# Mezclador2.net
KiCad netlist of a schematic drawn in Altium Designer
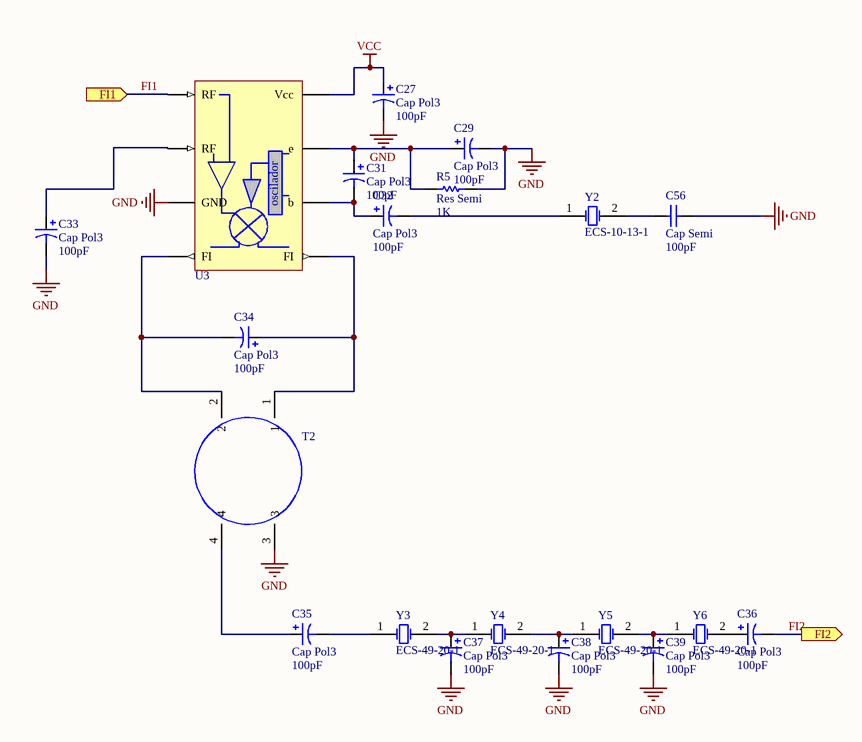
[diagram p0: Mezclador2.SchDoc]

(export (version "E")
  (design (tool "Eeschema 10.0.6"))
  (components
    (comp (ref "C27")
      (value "Cap Pol3")
      (footprint "C0805")
      (description "Polarized Capacitor (Surface Mount)")
      (fields (field (name "ALTIUM_VALUE") "100pF") (field (name "PUBLISHER") "Altium Limited"))
      (libsource (lib "Miscellaneous Devices") (part "Cap Pol3"))
    )
    (comp (ref "C29")
      (value "Cap Pol3")
      (footprint "C0805")
      (description "Polarized Capacitor (Surface Mount)")
      (fields (field (name "ALTIUM_VALUE") "100pF") (field (name "PUBLISHER") "Altium Limited"))
      (libsource (lib "Miscellaneous Devices") (part "Cap Pol3"))
    )
    (comp (ref "C31")
      (value "Cap Pol3")
      (footprint "C0805")
      (description "Polarized Capacitor (Surface Mount)")
      (fields (field (name "ALTIUM_VALUE") "100pF") (field (name "PUBLISHER") "Altium Limited"))
      (libsource (lib "Miscellaneous Devices") (part "Cap Pol3"))
    )
    (comp (ref "C32")
      (value "Cap Pol3")
      (footprint "C0805")
      (description "Polarized Capacitor (Surface Mount)")
      (fields (field (name "ALTIUM_VALUE") "100pF") (field (name "PUBLISHER") "Altium Limited"))
      (libsource (lib "Miscellaneous Devices") (part "Cap Pol3"))
    )
    (comp (ref "C33")
      (value "Cap Pol3")
      (footprint "C0805")
      (description "Polarized Capacitor (Surface Mount)")
      (fields (field (name "ALTIUM_VALUE") "100pF") (field (name "PUBLISHER") "Altium Limited"))
      (libsource (lib "Miscellaneous Devices") (part "Cap Pol3"))
    )
    (comp (ref "C34")
      (value "Cap Pol3")
      (footprint "C0805")
      (description "Polarized Capacitor (Surface Mount)")
      (fields (field (name "ALTIUM_VALUE") "100pF") (field (name "PUBLISHER") "Altium Limited"))
      (libsource (lib "Miscellaneous Devices") (part "Cap Pol3"))
    )
    (comp (ref "C35")
      (value "Cap Pol3")
      (footprint "C0805")
      (description "Polarized Capacitor (Surface Mount)")
      (fields (field (name "ALTIUM_VALUE") "100pF") (field (name "PUBLISHER") "Altium Limited"))
      (libsource (lib "Miscellaneous Devices") (part "Cap Pol3"))
    )
    (comp (ref "C36")
      (value "Cap Pol3")
      (footprint "C0805")
      (description "Polarized Capacitor (Surface Mount)")
      (fields (field (name "ALTIUM_VALUE") "100pF") (field (name "PUBLISHER") "Altium Limited"))
      (libsource (lib "Miscellaneous Devices") (part "Cap Pol3"))
    )
    (comp (ref "C37")
      (value "Cap Pol3")
      (footprint "C0805")
      (description "Polarized Capacitor (Surface Mount)")
      (fields (field (name "ALTIUM_VALUE") "100pF") (field (name "PUBLISHER") "Altium Limited"))
      (libsource (lib "Miscellaneous Devices") (part "Cap Pol3"))
    )
    (comp (ref "C38")
      (value "Cap Pol3")
      (footprint "C0805")
      (description "Polarized Capacitor (Surface Mount)")
      (fields (field (name "ALTIUM_VALUE") "100pF") (field (name "PUBLISHER") "Altium Limited"))
      (libsource (lib "Miscellaneous Devices") (part "Cap Pol3"))
    )
    (comp (ref "C39")
      (value "Cap Pol3")
      (footprint "C0805")
      (description "Polarized Capacitor (Surface Mount)")
      (fields (field (name "ALTIUM_VALUE") "100pF") (field (name "PUBLISHER") "Altium Limited"))
      (libsource (lib "Miscellaneous Devices") (part "Cap Pol3"))
    )
    (comp (ref "C56")
      (value "Cap Semi")
      (footprint "C1206")
      (description "Capacitor (Semiconductor SIM Model)")
      (fields (field (name "ALTIUM_VALUE") "100pF") (field (name "PUBLISHER") "Altium Limited"))
      (libsource (lib "Miscellaneous Devices") (part "Cap Semi"))
    )
    (comp (ref "R5")
      (value "Res Semi")
      (footprint "2012[0805]")
      (description "Semiconductor Resistor")
      (fields (field (name "ALTIUM_VALUE") "1K") (field (name "PUBLISHER") "Altium Limited"))
      (libsource (lib "Miscellaneous Devices") (part "Res Semi"))
    )
    (comp (ref "T2")
      (value "Toroide")
      (footprint "NTH12_4")
      (libsource (lib "epf") (part "Transformador_Toroide"))
    )
    (comp (ref "U3")
      (value "SA602")
      (footprint "SA602")
      (description "Mezclador 500MHz")
      (libsource (lib "epf") (part "SA602A"))
    )
    (comp (ref "Y2")
      (value "ECS-10-13-1")
      (footprint "HC-49U")
      (description "Crystal Oscillator")
      (fields (field (name "PUBLISHER") "Altium Limited"))
      (libsource (lib "ECS Crystal Oscillator") (part "ECS-10-13-1"))
    )
    (comp (ref "Y3")
      (value "ECS-49-20-1")
      (footprint "HC-49U")
      (description "Crystal Oscillator")
      (fields (field (name "PUBLISHER") "Altium Limited"))
      (libsource (lib "ECS Crystal Oscillator") (part "ECS-49-20-1"))
    )
    (comp (ref "Y4")
      (value "ECS-49-20-1")
      (footprint "HC-49U")
      (description "Crystal Oscillator")
      (fields (field (name "PUBLISHER") "Altium Limited"))
      (libsource (lib "ECS Crystal Oscillator") (part "ECS-49-20-1"))
    )
    (comp (ref "Y5")
      (value "ECS-49-20-1")
      (footprint "HC-49U")
      (description "Crystal Oscillator")
      (fields (field (name "PUBLISHER") "Altium Limited"))
      (libsource (lib "ECS Crystal Oscillator") (part "ECS-49-20-1"))
    )
    (comp (ref "Y6")
      (value "ECS-49-20-1")
      (footprint "HC-49U")
      (description "Crystal Oscillator")
      (fields (field (name "PUBLISHER") "Altium Limited"))
      (libsource (lib "ECS Crystal Oscillator") (part "ECS-49-20-1"))
    )
  )
  (nets
    (net (code "1") (name "/FI1") (class "Default")
      (node (ref "U3") (pin "1") (pinfunction "RF_1") (pintype "input"))
    )
    (net (code "2") (name "/FI2") (class "Default")
      (node (ref "C36") (pin "2") (pinfunction "2_2") (pintype "passive"))
    )
    (net (code "3") (name "GND") (class "Default")
      (node (ref "C27") (pin "2") (pinfunction "2_2") (pintype "passive"))
      (node (ref "C29") (pin "2") (pinfunction "2_2") (pintype "passive"))
      (node (ref "C33") (pin "2") (pinfunction "2_2") (pintype "passive"))
      (node (ref "C37") (pin "2") (pinfunction "2_2") (pintype "passive"))
      (node (ref "C38") (pin "2") (pinfunction "2_2") (pintype "passive"))
      (node (ref "C39") (pin "2") (pinfunction "2_2") (pintype "passive"))
      (node (ref "C56") (pin "2") (pinfunction "2_2") (pintype "passive"))
      (node (ref "R5") (pin "1") (pinfunction "1_1") (pintype "passive"))
      (node (ref "T2") (pin "3") (pinfunction "3_3") (pintype "passive"))
      (node (ref "U3") (pin "3") (pinfunction "GND_3") (pintype "passive"))
    )
    (net (code "4") (name "Net-(C33-Pad1)") (class "Default")
      (node (ref "C33") (pin "1") (pinfunction "1_1") (pintype "passive"))
      (node (ref "U3") (pin "2") (pinfunction "RF_2") (pintype "input"))
    )
    (net (code "5") (name "Net-(C34-Pad1)") (class "Default")
      (node (ref "C34") (pin "1") (pinfunction "1_1") (pintype "passive"))
      (node (ref "T2") (pin "1") (pinfunction "1_1") (pintype "passive"))
      (node (ref "U3") (pin "5") (pinfunction "FI_5") (pintype "output"))
    )
    (net (code "6") (name "Net-(C34-Pad2)") (class "Default")
      (node (ref "C34") (pin "2") (pinfunction "2_2") (pintype "passive"))
      (node (ref "T2") (pin "2") (pinfunction "2_2") (pintype "passive"))
      (node (ref "U3") (pin "4") (pinfunction "FI_4") (pintype "output"))
    )
    (net (code "7") (name "Net-(C35-Pad1)") (class "Default")
      (node (ref "C35") (pin "1") (pinfunction "1_1") (pintype "passive"))
      (node (ref "T2") (pin "4") (pinfunction "4_4") (pintype "passive"))
    )
    (net (code "8") (name "Net-(U3-b)") (class "Default")
      (node (ref "C31") (pin "2") (pinfunction "2_2") (pintype "passive"))
      (node (ref "C32") (pin "1") (pinfunction "1_1") (pintype "passive"))
      (node (ref "U3") (pin "6") (pinfunction "b_6") (pintype "passive"))
    )
    (net (code "9") (name "Net-(U3-e)") (class "Default")
      (node (ref "C29") (pin "1") (pinfunction "1_1") (pintype "passive"))
      (node (ref "C31") (pin "1") (pinfunction "1_1") (pintype "passive"))
      (node (ref "R5") (pin "2") (pinfunction "2_2") (pintype "passive"))
      (node (ref "U3") (pin "7") (pinfunction "e_7") (pintype "passive"))
    )
    (net (code "10") (name "Net-(Y2-OSC1)") (class "Default")
      (node (ref "C32") (pin "2") (pinfunction "2_2") (pintype "passive"))
      (node (ref "Y2") (pin "1") (pinfunction "OSC1_1") (pintype "passive"))
    )
    (net (code "11") (name "Net-(Y2-OSC2)") (class "Default")
      (node (ref "C56") (pin "1") (pinfunction "1_1") (pintype "passive"))
      (node (ref "Y2") (pin "2") (pinfunction "OSC2_2") (pintype "passive"))
    )
    (net (code "12") (name "Net-(Y3-OSC1)") (class "Default")
      (node (ref "C35") (pin "2") (pinfunction "2_2") (pintype "passive"))
      (node (ref "Y3") (pin "1") (pinfunction "OSC1_1") (pintype "passive"))
    )
    (net (code "13") (name "Net-(Y3-OSC2)") (class "Default")
      (node (ref "C37") (pin "1") (pinfunction "1_1") (pintype "passive"))
      (node (ref "Y3") (pin "2") (pinfunction "OSC2_2") (pintype "passive"))
      (node (ref "Y4") (pin "1") (pinfunction "OSC1_1") (pintype "passive"))
    )
    (net (code "14") (name "Net-(Y4-OSC2)") (class "Default")
      (node (ref "C38") (pin "1") (pinfunction "1_1") (pintype "passive"))
      (node (ref "Y4") (pin "2") (pinfunction "OSC2_2") (pintype "passive"))
      (node (ref "Y5") (pin "1") (pinfunction "OSC1_1") (pintype "passive"))
    )
    (net (code "15") (name "Net-(Y5-OSC2)") (class "Default")
      (node (ref "C39") (pin "1") (pinfunction "1_1") (pintype "passive"))
      (node (ref "Y5") (pin "2") (pinfunction "OSC2_2") (pintype "passive"))
      (node (ref "Y6") (pin "1") (pinfunction "OSC1_1") (pintype "passive"))
    )
    (net (code "16") (name "Net-(Y6-OSC2)") (class "Default")
      (node (ref "C36") (pin "1") (pinfunction "1_1") (pintype "passive"))
      (node (ref "Y6") (pin "2") (pinfunction "OSC2_2") (pintype "passive"))
    )
    (net (code "17") (name "VCC") (class "Default")
      (node (ref "C27") (pin "1") (pinfunction "1_1") (pintype "passive"))
      (node (ref "U3") (pin "8") (pinfunction "Vcc_8") (pintype "passive"))
    )
  )
)
